# Buckconverter.net
KiCad netlist of a schematic drawn in EAGLE
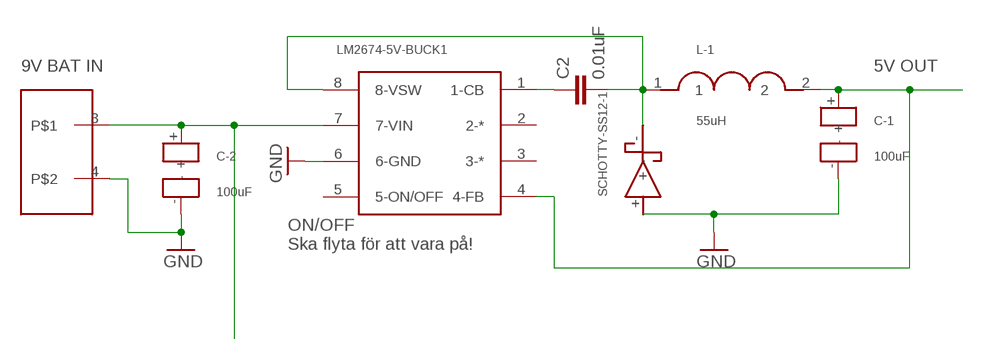
[diagram p0: schematic, sheet 1]

(export (version "E")
  (design (tool "Eeschema 10.0.6"))
  (components
    (comp (ref "C-1")
      (value "100uF")
      (footprint "eagle-import:CAP-6.3MM-DIA")
      (libsource (lib "eagle-import") (part "PANASONIC-CAP"))
    )
    (comp (ref "C-2")
      (value "100uF")
      (footprint "eagle-import:CAP-6.3MM-DIA")
      (libsource (lib "eagle-import") (part "PANASONIC-CAP"))
    )
    (comp (ref "C2")
      (value "0.01uF")
      (footprint "eagle-import:C0805")
      (libsource (lib "eagle-import") (part "C-EUC0805"))
    )
    (comp (ref "L-1")
      (value "55uH")
      (footprint "eagle-import:INDUCTOR")
      (libsource (lib "eagle-import") (part "55UH-INDUKTOR"))
    )
    (comp (ref "LM2674-5V-BUCK1")
      (value "LM2674-5VBUCK")
      (footprint "eagle-import:LM2674")
      (libsource (lib "eagle-import") (part "LM2674-5VBUCK"))
    )
    (comp (ref "SCHOTTY-SS12-1")
      (value "SCHOTTY-SS12")
      (footprint "eagle-import:SCHOTTY")
      (libsource (lib "eagle-import") (part "SCHOTTY-SS12"))
    )
    (comp (ref "SKRUVPLINT_2P1")
      (value "SKRUVPLINT_2P")
      (footprint "eagle-import:SKRUVPLINT_2P")
      (libsource (lib "eagle-import") (part "SKRUVPLINT_2P"))
    )
  )
  (nets
    (net (code "1") (name "GND") (class "Default")
      (node (ref "C-1") (pin "-") (pinfunction "-_-") (pintype "bidirectional"))
      (node (ref "C-2") (pin "-") (pinfunction "-_-") (pintype "bidirectional"))
      (node (ref "LM2674-5V-BUCK1") (pin "6") (pinfunction "6-GND_6") (pintype "bidirectional"))
      (node (ref "SCHOTTY-SS12-1") (pin "+") (pinfunction "+_+") (pintype "bidirectional"))
      (node (ref "SKRUVPLINT_2P1") (pin "4") (pinfunction "P$2_4") (pintype "bidirectional"))
    )
    (net (code "2") (name "Net-(LM2674-5V-BUCK1-1-CB)") (class "Default")
      (node (ref "C2") (pin "1") (pinfunction "1_1") (pintype "passive"))
      (node (ref "LM2674-5V-BUCK1") (pin "1") (pinfunction "1-CB_1") (pintype "bidirectional"))
    )
    (net (code "3") (name "Net-(LM2674-5V-BUCK1-4-FB)") (class "Default")
      (node (ref "C-1") (pin "+") (pinfunction "+_+") (pintype "bidirectional"))
      (node (ref "L-1") (pin "2") (pinfunction "2_2") (pintype "bidirectional"))
      (node (ref "LM2674-5V-BUCK1") (pin "4") (pinfunction "4-FB_4") (pintype "bidirectional"))
    )
    (net (code "4") (name "Net-(LM2674-5V-BUCK1-7-VIN)") (class "Default")
      (node (ref "C-2") (pin "+") (pinfunction "+_+") (pintype "bidirectional"))
      (node (ref "LM2674-5V-BUCK1") (pin "7") (pinfunction "7-VIN_7") (pintype "bidirectional"))
      (node (ref "SKRUVPLINT_2P1") (pin "3") (pinfunction "P$1_3") (pintype "bidirectional"))
    )
    (net (code "5") (name "Net-(LM2674-5V-BUCK1-8-VSW)") (class "Default")
      (node (ref "C2") (pin "2") (pinfunction "2_2") (pintype "passive"))
      (node (ref "L-1") (pin "1") (pinfunction "1_1") (pintype "bidirectional"))
      (node (ref "LM2674-5V-BUCK1") (pin "8") (pinfunction "8-VSW_8") (pintype "bidirectional"))
      (node (ref "SCHOTTY-SS12-1") (pin "-") (pinfunction "-_-") (pintype "bidirectional"))
    )
    (net (code "6") (name "unconnected-(LM2674-5V-BUCK1-2-*-Pad2)") (class "Default")
      (node (ref "LM2674-5V-BUCK1") (pin "2") (pinfunction "2-*_2") (pintype "bidirectional"))
    )
    (net (code "7") (name "unconnected-(LM2674-5V-BUCK1-3-*-Pad3)") (class "Default")
      (node (ref "LM2674-5V-BUCK1") (pin "3") (pinfunction "3-*_3") (pintype "bidirectional"))
    )
    (net (code "8") (name "unconnected-(LM2674-5V-BUCK1-5-ON{slash}OFF-Pad5)") (class "Default")
      (node (ref "LM2674-5V-BUCK1") (pin "5") (pinfunction "5-ON/OFF_5") (pintype "bidirectional"))
    )
  )
)
